# riffle-CTL-0_2-blank.net
KiCad netlist of a schematic drawn in EAGLE
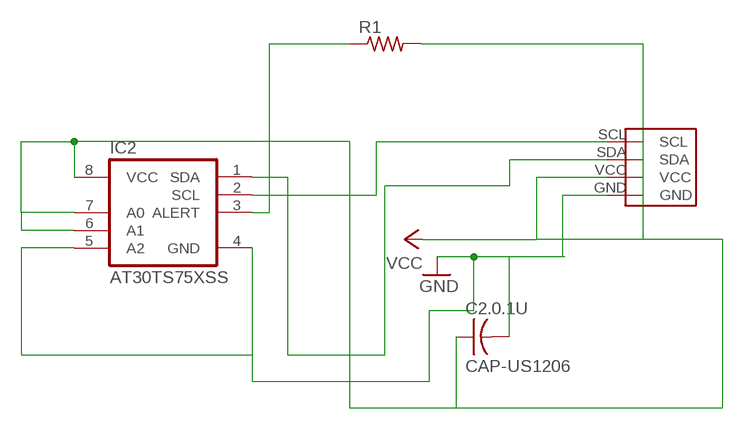
[diagram p0: schematic, sheet 1]

(export (version "E")
  (design (tool "Eeschema 10.0.6"))
  (components
    (comp (ref "C2.0.1U")
      (value "CAP-US1206")
      (footprint "eagle-import:C1206")
      (libsource (lib "eagle-import") (part "CAP-US1206"))
    )
    (comp (ref "IC2")
      (value "AT30TS75XSS")
      (footprint "eagle-import:SO8")
      (libsource (lib "eagle-import") (part "AT30TS75XSS"))
    )
    (comp (ref "R1")
      (value "RES-US1206")
      (footprint "eagle-import:R1206")
      (libsource (lib "eagle-import") (part "RES-US1206"))
    )
    (comp (ref "U$3")
      (value "4PINHEADERTHROUGHHOLE")
      (footprint "eagle-import:1X04THROUGHHOLE")
      (libsource (lib "eagle-import") (part "4PINHEADERTHROUGHHOLE"))
    )
  )
  (nets
    (net (code "1") (name "GND") (class "Default")
      (node (ref "C2.0.1U") (pin "2") (pinfunction "2_2") (pintype "passive"))
      (node (ref "IC2") (pin "4") (pinfunction "GND_4") (pintype "power_in"))
      (node (ref "IC2") (pin "5") (pinfunction "A2_5") (pintype "input"))
      (node (ref "U$3") (pin "GND") (pinfunction "GND_GND") (pintype "bidirectional"))
    )
    (net (code "2") (name "Net-(IC2-ALERT)") (class "Default")
      (node (ref "IC2") (pin "3") (pinfunction "ALERT_3") (pintype "output"))
      (node (ref "R1") (pin "1") (pinfunction "1_1") (pintype "passive"))
    )
    (net (code "3") (name "Net-(IC2-SCL)") (class "Default")
      (node (ref "IC2") (pin "2") (pinfunction "SCL_2") (pintype "input"))
      (node (ref "U$3") (pin "SCL") (pinfunction "SCL_SCL") (pintype "bidirectional"))
    )
    (net (code "4") (name "Net-(IC2-SDA)") (class "Default")
      (node (ref "IC2") (pin "1") (pinfunction "SDA_1") (pintype "bidirectional"))
      (node (ref "U$3") (pin "SDA") (pinfunction "SDA_SDA") (pintype "bidirectional"))
    )
    (net (code "5") (name "VCC") (class "Default")
      (node (ref "C2.0.1U") (pin "1") (pinfunction "1_1") (pintype "passive"))
      (node (ref "IC2") (pin "6") (pinfunction "A1_6") (pintype "input"))
      (node (ref "IC2") (pin "7") (pinfunction "A0_7") (pintype "input"))
      (node (ref "IC2") (pin "8") (pinfunction "VCC_8") (pintype "power_in"))
      (node (ref "R1") (pin "2") (pinfunction "2_2") (pintype "passive"))
      (node (ref "U$3") (pin "VCC") (pinfunction "VCC_VCC") (pintype "bidirectional"))
    )
  )
)
